# shield_Arduino.net
KiCad netlist of a schematic drawn in EAGLE
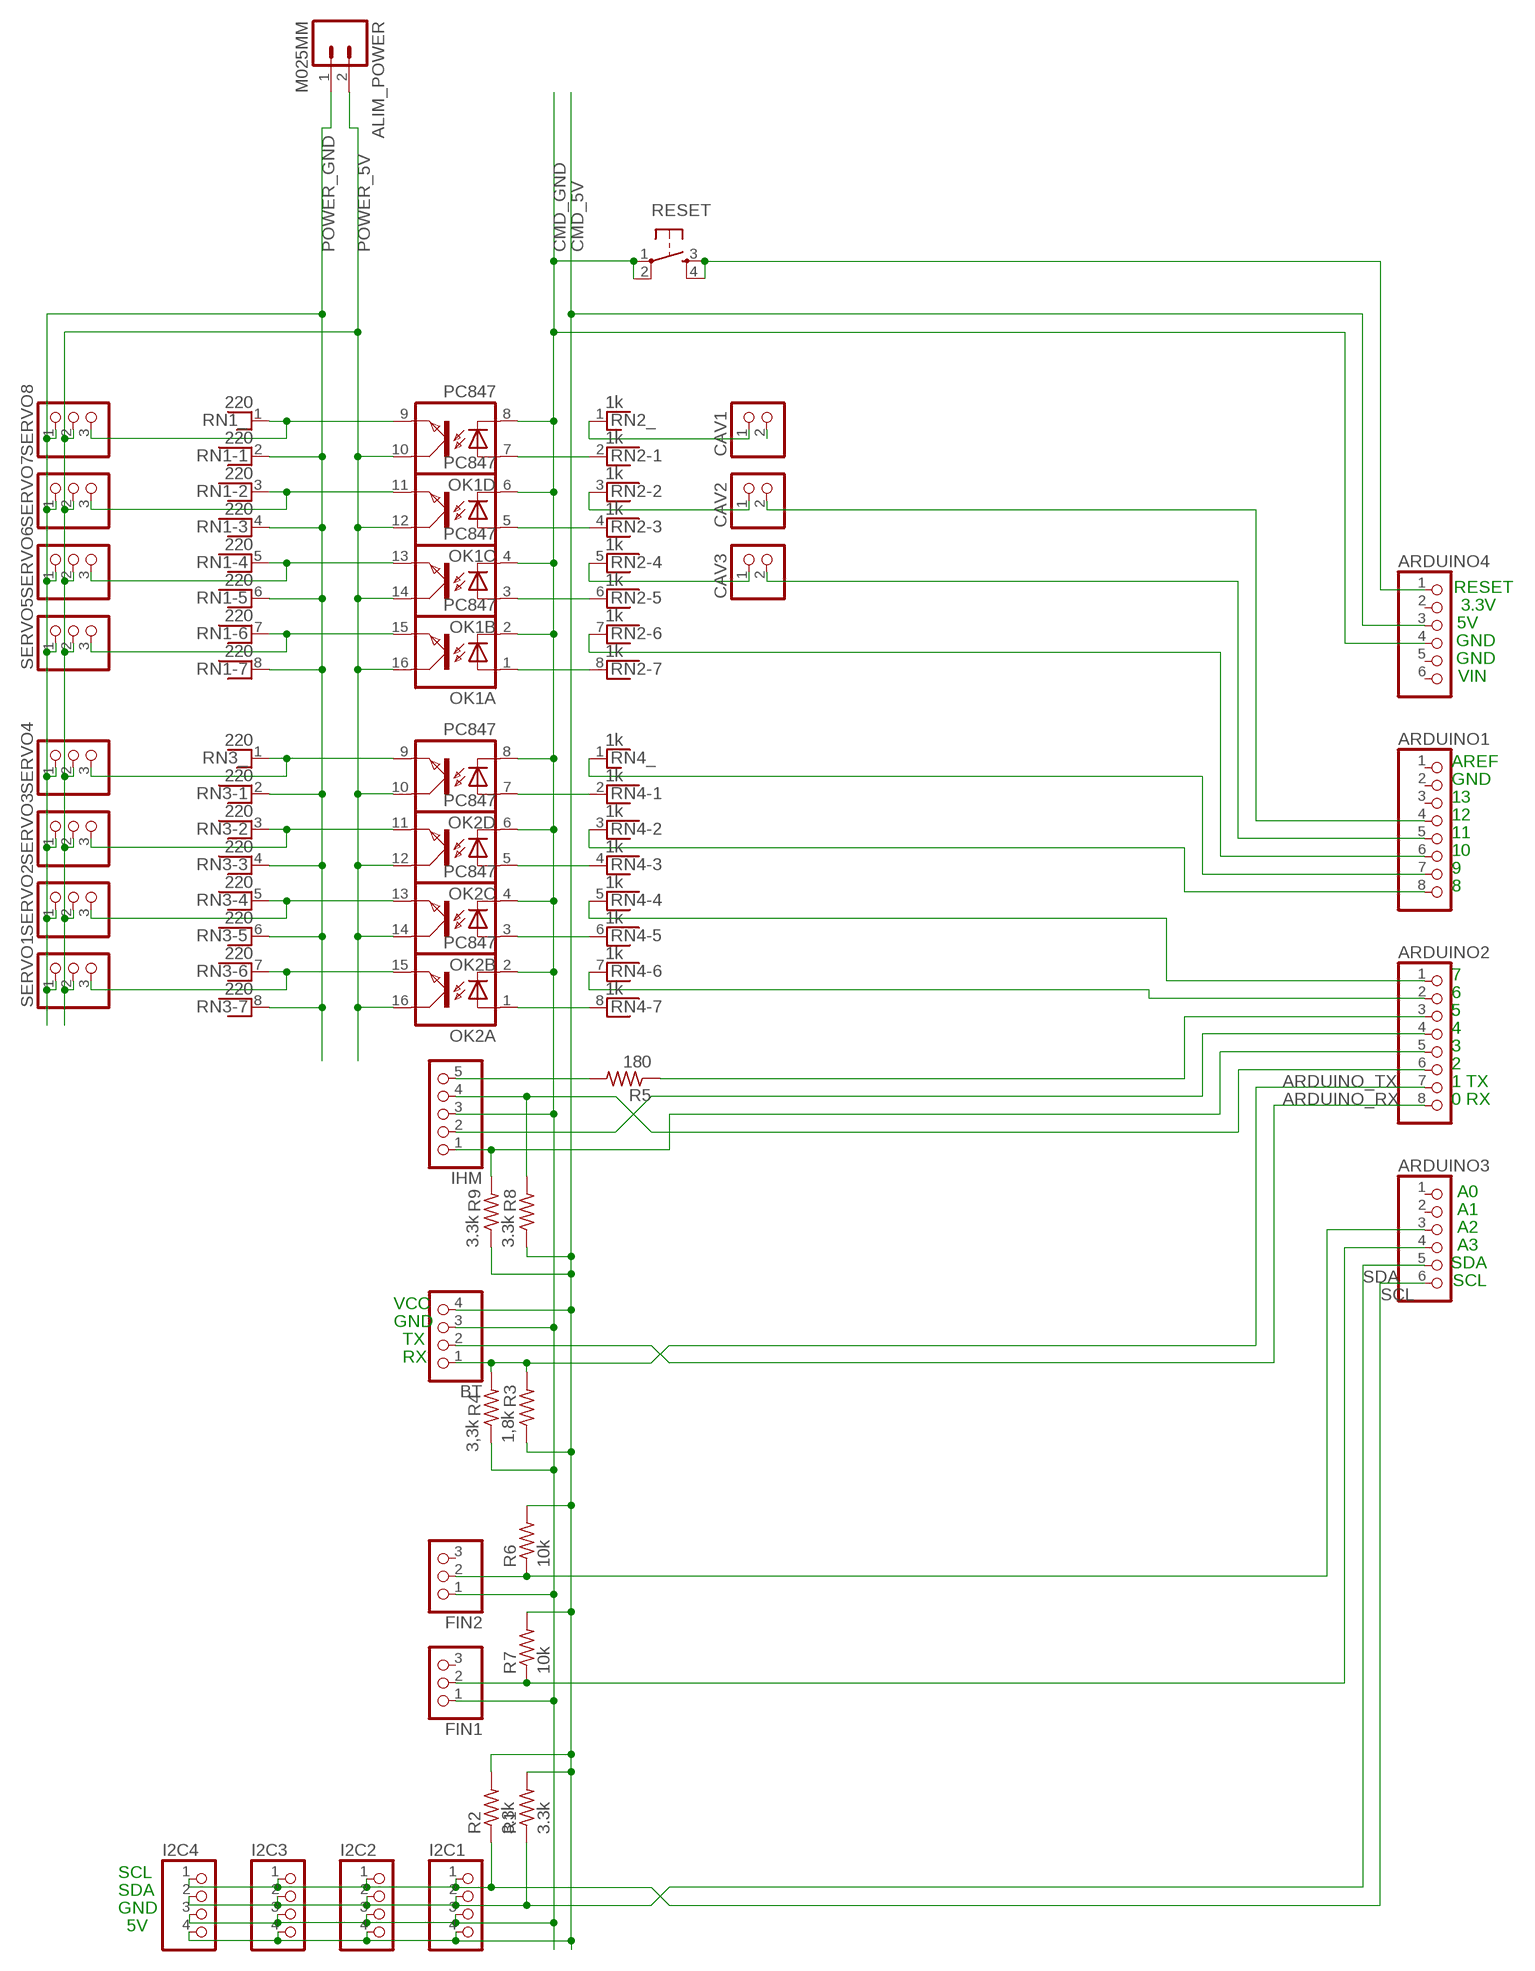
[diagram p0: schematic, sheet 1]

(export (version "E")
  (design (tool "Eeschema 10.0.6"))
  (components
    (comp (ref "ALIM_POWER")
      (value "M025MM")
      (footprint "eagle-import:SCREWTERMINAL-5MM-2")
      (libsource (lib "eagle-import") (part "M025MM"))
    )
    (comp (ref "ARDUINO1")
      (value "PINHD-1X8")
      (footprint "eagle-import:1X08")
      (libsource (lib "eagle-import") (part "PINHD-1X8"))
    )
    (comp (ref "ARDUINO2")
      (value "PINHD-1X8")
      (footprint "eagle-import:1X08")
      (libsource (lib "eagle-import") (part "PINHD-1X8"))
    )
    (comp (ref "ARDUINO3")
      (value "PINHD-1X6")
      (footprint "eagle-import:1X06")
      (libsource (lib "eagle-import") (part "PINHD-1X6"))
    )
    (comp (ref "ARDUINO4")
      (value "PINHD-1X6")
      (footprint "eagle-import:1X06")
      (libsource (lib "eagle-import") (part "PINHD-1X6"))
    )
    (comp (ref "BT")
      (value "PINHD-1X4")
      (footprint "eagle-import:1X04")
      (libsource (lib "eagle-import") (part "PINHD-1X4"))
    )
    (comp (ref "CAV1")
      (value "PINHD-1X2")
      (footprint "eagle-import:1X02")
      (libsource (lib "eagle-import") (part "PINHD-1X2"))
    )
    (comp (ref "CAV2")
      (value "PINHD-1X2")
      (footprint "eagle-import:1X02")
      (libsource (lib "eagle-import") (part "PINHD-1X2"))
    )
    (comp (ref "CAV3")
      (value "PINHD-1X2")
      (footprint "eagle-import:1X02")
      (libsource (lib "eagle-import") (part "PINHD-1X2"))
    )
    (comp (ref "FIN1")
      (value "PINHD-1X3")
      (footprint "eagle-import:1X03")
      (libsource (lib "eagle-import") (part "PINHD-1X3"))
    )
    (comp (ref "FIN2")
      (value "PINHD-1X3")
      (footprint "eagle-import:1X03")
      (libsource (lib "eagle-import") (part "PINHD-1X3"))
    )
    (comp (ref "I2C1")
      (value "PINHD-1X4")
      (footprint "eagle-import:1X04")
      (libsource (lib "eagle-import") (part "PINHD-1X4"))
    )
    (comp (ref "I2C2")
      (value "PINHD-1X4")
      (footprint "eagle-import:1X04")
      (libsource (lib "eagle-import") (part "PINHD-1X4"))
    )
    (comp (ref "I2C3")
      (value "PINHD-1X4")
      (footprint "eagle-import:1X04")
      (libsource (lib "eagle-import") (part "PINHD-1X4"))
    )
    (comp (ref "I2C4")
      (value "PINHD-1X4")
      (footprint "eagle-import:1X04")
      (libsource (lib "eagle-import") (part "PINHD-1X4"))
    )
    (comp (ref "IHM")
      (value "PINHD-1X5")
      (footprint "eagle-import:1X05")
      (libsource (lib "eagle-import") (part "PINHD-1X5"))
    )
    (comp (ref "OK1")
      (value "PC847")
      (footprint "eagle-import:DIL16")
      (libsource (lib "eagle-import") (part "PC847"))
    )
    (comp (ref "OK2")
      (value "PC847")
      (footprint "eagle-import:DIL16")
      (libsource (lib "eagle-import") (part "PC847"))
    )
    (comp (ref "R1")
      (value "3.3k")
      (footprint "eagle-import:0204_7")
      (libsource (lib "eagle-import") (part "R-US_0204/7"))
    )
    (comp (ref "R2")
      (value "3.3k")
      (footprint "eagle-import:0204_7")
      (libsource (lib "eagle-import") (part "R-US_0204/7"))
    )
    (comp (ref "R3")
      (value "1,8k")
      (footprint "eagle-import:0204_7")
      (libsource (lib "eagle-import") (part "R-US_0204/7"))
    )
    (comp (ref "R4")
      (value "3,3k")
      (footprint "eagle-import:0204_7")
      (libsource (lib "eagle-import") (part "R-US_0204/7"))
    )
    (comp (ref "R5")
      (value "180")
      (footprint "eagle-import:0204_7")
      (libsource (lib "eagle-import") (part "R-US_0204/7"))
    )
    (comp (ref "R6")
      (value "10k")
      (footprint "eagle-import:0204_7")
      (libsource (lib "eagle-import") (part "R-US_0204/7"))
    )
    (comp (ref "R7")
      (value "10k")
      (footprint "eagle-import:0204_7")
      (libsource (lib "eagle-import") (part "R-US_0204/7"))
    )
    (comp (ref "R8")
      (value "3.3k")
      (footprint "eagle-import:0204_7")
      (libsource (lib "eagle-import") (part "R-US_0204/7"))
    )
    (comp (ref "R9")
      (value "3.3k")
      (footprint "eagle-import:0204_7")
      (libsource (lib "eagle-import") (part "R-US_0204/7"))
    )
    (comp (ref "RESET")
      (value "TAC_SWITCHPTH")
      (footprint "eagle-import:TACTILE-PTH")
      (libsource (lib "eagle-import") (part "TAC_SWITCHPTH"))
    )
    (comp (ref "RN1")
      (value "220")
      (footprint "eagle-import:RN-8")
      (libsource (lib "eagle-import") (part "RNX7"))
    )
    (comp (ref "RN2")
      (value "1k")
      (footprint "eagle-import:RN-8")
      (libsource (lib "eagle-import") (part "RNX7"))
    )
    (comp (ref "RN3")
      (value "220")
      (footprint "eagle-import:RN-8")
      (libsource (lib "eagle-import") (part "RNX7"))
    )
    (comp (ref "RN4")
      (value "1k")
      (footprint "eagle-import:RN-8")
      (libsource (lib "eagle-import") (part "RNX7"))
    )
    (comp (ref "SERVO1")
      (value "PINHD-1X3")
      (footprint "eagle-import:1X03")
      (libsource (lib "eagle-import") (part "PINHD-1X3"))
    )
    (comp (ref "SERVO2")
      (value "PINHD-1X3")
      (footprint "eagle-import:1X03")
      (libsource (lib "eagle-import") (part "PINHD-1X3"))
    )
    (comp (ref "SERVO3")
      (value "PINHD-1X3")
      (footprint "eagle-import:1X03")
      (libsource (lib "eagle-import") (part "PINHD-1X3"))
    )
    (comp (ref "SERVO4")
      (value "PINHD-1X3")
      (footprint "eagle-import:1X03")
      (libsource (lib "eagle-import") (part "PINHD-1X3"))
    )
    (comp (ref "SERVO5")
      (value "PINHD-1X3")
      (footprint "eagle-import:1X03")
      (libsource (lib "eagle-import") (part "PINHD-1X3"))
    )
    (comp (ref "SERVO6")
      (value "PINHD-1X3")
      (footprint "eagle-import:1X03")
      (libsource (lib "eagle-import") (part "PINHD-1X3"))
    )
    (comp (ref "SERVO7")
      (value "PINHD-1X3")
      (footprint "eagle-import:1X03")
      (libsource (lib "eagle-import") (part "PINHD-1X3"))
    )
    (comp (ref "SERVO8")
      (value "PINHD-1X3")
      (footprint "eagle-import:1X03")
      (libsource (lib "eagle-import") (part "PINHD-1X3"))
    )
  )
  (nets
    (net (code "1") (name "/ARDUINO_RX") (class "Default")
      (node (ref "ARDUINO2") (pin "8") (pinfunction "8_8") (pintype "passive"))
      (node (ref "BT") (pin "2") (pinfunction "2_2") (pintype "passive"))
    )
    (net (code "2") (name "/ARDUINO_TX") (class "Default")
      (node (ref "ARDUINO2") (pin "7") (pinfunction "7_7") (pintype "passive"))
      (node (ref "BT") (pin "1") (pinfunction "1_1") (pintype "passive"))
      (node (ref "R3") (pin "2") (pinfunction "2_2") (pintype "passive"))
      (node (ref "R4") (pin "2") (pinfunction "2_2") (pintype "passive"))
    )
    (net (code "3") (name "/CMD_5V") (class "Default")
      (node (ref "ARDUINO4") (pin "3") (pinfunction "3_3") (pintype "passive"))
      (node (ref "BT") (pin "4") (pinfunction "4_4") (pintype "passive"))
      (node (ref "I2C1") (pin "4") (pinfunction "4_4") (pintype "passive"))
      (node (ref "I2C2") (pin "4") (pinfunction "4_4") (pintype "passive"))
      (node (ref "I2C3") (pin "4") (pinfunction "4_4") (pintype "passive"))
      (node (ref "I2C4") (pin "4") (pinfunction "4_4") (pintype "passive"))
      (node (ref "R1") (pin "2") (pinfunction "2_2") (pintype "passive"))
      (node (ref "R2") (pin "2") (pinfunction "2_2") (pintype "passive"))
      (node (ref "R3") (pin "1") (pinfunction "1_1") (pintype "passive"))
      (node (ref "R6") (pin "2") (pinfunction "2_2") (pintype "passive"))
      (node (ref "R7") (pin "2") (pinfunction "2_2") (pintype "passive"))
      (node (ref "R8") (pin "1") (pinfunction "1_1") (pintype "passive"))
      (node (ref "R9") (pin "1") (pinfunction "1_1") (pintype "passive"))
    )
    (net (code "4") (name "/CMD_GND") (class "Default")
      (node (ref "ARDUINO4") (pin "4") (pinfunction "4_4") (pintype "passive"))
      (node (ref "BT") (pin "3") (pinfunction "3_3") (pintype "passive"))
      (node (ref "FIN1") (pin "1") (pinfunction "1_1") (pintype "passive"))
      (node (ref "FIN2") (pin "1") (pinfunction "1_1") (pintype "passive"))
      (node (ref "I2C1") (pin "3") (pinfunction "3_3") (pintype "passive"))
      (node (ref "I2C2") (pin "3") (pinfunction "3_3") (pintype "passive"))
      (node (ref "I2C3") (pin "3") (pinfunction "3_3") (pintype "passive"))
      (node (ref "I2C4") (pin "3") (pinfunction "3_3") (pintype "passive"))
      (node (ref "IHM") (pin "3") (pinfunction "3_3") (pintype "passive"))
      (node (ref "OK1") (pin "2") (pinfunction "C_2") (pintype "passive"))
      (node (ref "OK1") (pin "4") (pinfunction "C_4") (pintype "passive"))
      (node (ref "OK1") (pin "6") (pinfunction "C_6") (pintype "passive"))
      (node (ref "OK1") (pin "8") (pinfunction "C_8") (pintype "passive"))
      (node (ref "OK2") (pin "2") (pinfunction "C_2") (pintype "passive"))
      (node (ref "OK2") (pin "4") (pinfunction "C_4") (pintype "passive"))
      (node (ref "OK2") (pin "6") (pinfunction "C_6") (pintype "passive"))
      (node (ref "OK2") (pin "8") (pinfunction "C_8") (pintype "passive"))
      (node (ref "R4") (pin "1") (pinfunction "1_1") (pintype "passive"))
      (node (ref "RESET") (pin "1") (pinfunction "1_1") (pintype "passive"))
      (node (ref "RESET") (pin "2") (pinfunction "2_2") (pintype "passive"))
    )
    (net (code "5") (name "/POWER_5V") (class "Default")
      (node (ref "ALIM_POWER") (pin "2") (pinfunction "2_2") (pintype "passive"))
      (node (ref "OK1") (pin "10") (pinfunction "COL_10") (pintype "passive"))
      (node (ref "OK1") (pin "12") (pinfunction "COL_12") (pintype "passive"))
      (node (ref "OK1") (pin "14") (pinfunction "COL_14") (pintype "passive"))
      (node (ref "OK1") (pin "16") (pinfunction "COL_16") (pintype "passive"))
      (node (ref "OK2") (pin "10") (pinfunction "COL_10") (pintype "passive"))
      (node (ref "OK2") (pin "12") (pinfunction "COL_12") (pintype "passive"))
      (node (ref "OK2") (pin "14") (pinfunction "COL_14") (pintype "passive"))
      (node (ref "OK2") (pin "16") (pinfunction "COL_16") (pintype "passive"))
      (node (ref "SERVO1") (pin "2") (pinfunction "2_2") (pintype "passive"))
      (node (ref "SERVO2") (pin "2") (pinfunction "2_2") (pintype "passive"))
      (node (ref "SERVO3") (pin "2") (pinfunction "2_2") (pintype "passive"))
      (node (ref "SERVO4") (pin "2") (pinfunction "2_2") (pintype "passive"))
      (node (ref "SERVO5") (pin "2") (pinfunction "2_2") (pintype "passive"))
      (node (ref "SERVO6") (pin "2") (pinfunction "2_2") (pintype "passive"))
      (node (ref "SERVO7") (pin "2") (pinfunction "2_2") (pintype "passive"))
      (node (ref "SERVO8") (pin "2") (pinfunction "2_2") (pintype "passive"))
    )
    (net (code "6") (name "/POWER_GND") (class "Default")
      (node (ref "ALIM_POWER") (pin "1") (pinfunction "1_1") (pintype "passive"))
      (node (ref "RN1") (pin "2") (pinfunction "1_2") (pintype "passive"))
      (node (ref "RN1") (pin "4") (pinfunction "1_4") (pintype "passive"))
      (node (ref "RN1") (pin "6") (pinfunction "1_6") (pintype "passive"))
      (node (ref "RN1") (pin "8") (pinfunction "1_8") (pintype "passive"))
      (node (ref "RN3") (pin "2") (pinfunction "1_2") (pintype "passive"))
      (node (ref "RN3") (pin "4") (pinfunction "1_4") (pintype "passive"))
      (node (ref "RN3") (pin "6") (pinfunction "1_6") (pintype "passive"))
      (node (ref "RN3") (pin "8") (pinfunction "1_8") (pintype "passive"))
      (node (ref "SERVO1") (pin "1") (pinfunction "1_1") (pintype "passive"))
      (node (ref "SERVO2") (pin "1") (pinfunction "1_1") (pintype "passive"))
      (node (ref "SERVO3") (pin "1") (pinfunction "1_1") (pintype "passive"))
      (node (ref "SERVO4") (pin "1") (pinfunction "1_1") (pintype "passive"))
      (node (ref "SERVO5") (pin "1") (pinfunction "1_1") (pintype "passive"))
      (node (ref "SERVO6") (pin "1") (pinfunction "1_1") (pintype "passive"))
      (node (ref "SERVO7") (pin "1") (pinfunction "1_1") (pintype "passive"))
      (node (ref "SERVO8") (pin "1") (pinfunction "1_1") (pintype "passive"))
    )
    (net (code "7") (name "/SCL") (class "Default")
      (node (ref "ARDUINO3") (pin "6") (pinfunction "6_6") (pintype "passive"))
      (node (ref "I2C1") (pin "1") (pinfunction "1_1") (pintype "passive"))
      (node (ref "I2C2") (pin "1") (pinfunction "1_1") (pintype "passive"))
      (node (ref "I2C3") (pin "1") (pinfunction "1_1") (pintype "passive"))
      (node (ref "I2C4") (pin "1") (pinfunction "1_1") (pintype "passive"))
      (node (ref "R2") (pin "1") (pinfunction "1_1") (pintype "passive"))
    )
    (net (code "8") (name "/SDA") (class "Default")
      (node (ref "ARDUINO3") (pin "5") (pinfunction "5_5") (pintype "passive"))
      (node (ref "I2C1") (pin "2") (pinfunction "2_2") (pintype "passive"))
      (node (ref "I2C2") (pin "2") (pinfunction "2_2") (pintype "passive"))
      (node (ref "I2C3") (pin "2") (pinfunction "2_2") (pintype "passive"))
      (node (ref "I2C4") (pin "2") (pinfunction "2_2") (pintype "passive"))
      (node (ref "R1") (pin "1") (pinfunction "1_1") (pintype "passive"))
    )
    (net (code "9") (name "Net-(ARDUINO1-Pad4)") (class "Default")
      (node (ref "ARDUINO1") (pin "4") (pinfunction "4_4") (pintype "passive"))
      (node (ref "CAV2") (pin "2") (pinfunction "2_2") (pintype "passive"))
    )
    (net (code "10") (name "Net-(ARDUINO1-Pad5)") (class "Default")
      (node (ref "ARDUINO1") (pin "5") (pinfunction "5_5") (pintype "passive"))
      (node (ref "CAV3") (pin "2") (pinfunction "2_2") (pintype "passive"))
    )
    (net (code "11") (name "Net-(ARDUINO1-Pad7)") (class "Default")
      (node (ref "ARDUINO1") (pin "7") (pinfunction "7_7") (pintype "passive"))
      (node (ref "RN4") (pin "1") (pinfunction "1_1") (pintype "passive"))
    )
    (net (code "12") (name "Net-(ARDUINO2-Pad3)") (class "Default")
      (node (ref "ARDUINO2") (pin "3") (pinfunction "3_3") (pintype "passive"))
      (node (ref "R5") (pin "1") (pinfunction "1_1") (pintype "passive"))
    )
    (net (code "13") (name "Net-(ARDUINO2-Pad4)") (class "Default")
      (node (ref "ARDUINO2") (pin "4") (pinfunction "4_4") (pintype "passive"))
      (node (ref "IHM") (pin "2") (pinfunction "2_2") (pintype "passive"))
    )
    (net (code "14") (name "Net-(ARDUINO2-Pad5)") (class "Default")
      (node (ref "ARDUINO2") (pin "5") (pinfunction "5_5") (pintype "passive"))
      (node (ref "IHM") (pin "1") (pinfunction "1_1") (pintype "passive"))
      (node (ref "R9") (pin "2") (pinfunction "2_2") (pintype "passive"))
    )
    (net (code "15") (name "Net-(ARDUINO2-Pad6)") (class "Default")
      (node (ref "ARDUINO2") (pin "6") (pinfunction "6_6") (pintype "passive"))
      (node (ref "IHM") (pin "4") (pinfunction "4_4") (pintype "passive"))
      (node (ref "R8") (pin "2") (pinfunction "2_2") (pintype "passive"))
    )
    (net (code "16") (name "Net-(ARDUINO3-Pad3)") (class "Default")
      (node (ref "ARDUINO3") (pin "3") (pinfunction "3_3") (pintype "passive"))
      (node (ref "FIN2") (pin "2") (pinfunction "2_2") (pintype "passive"))
      (node (ref "R6") (pin "1") (pinfunction "1_1") (pintype "passive"))
    )
    (net (code "17") (name "Net-(ARDUINO3-Pad4)") (class "Default")
      (node (ref "ARDUINO3") (pin "4") (pinfunction "4_4") (pintype "passive"))
      (node (ref "FIN1") (pin "2") (pinfunction "2_2") (pintype "passive"))
      (node (ref "R7") (pin "1") (pinfunction "1_1") (pintype "passive"))
    )
    (net (code "18") (name "Net-(ARDUINO4-Pad1)") (class "Default")
      (node (ref "ARDUINO4") (pin "1") (pinfunction "1_1") (pintype "passive"))
      (node (ref "RESET") (pin "3") (pinfunction "3_3") (pintype "passive"))
      (node (ref "RESET") (pin "4") (pinfunction "4_4") (pintype "passive"))
    )
    (net (code "19") (name "Net-(CAV1-Pad1)") (class "Default")
      (node (ref "CAV1") (pin "1") (pinfunction "1_1") (pintype "passive"))
      (node (ref "RN2") (pin "1") (pinfunction "1_1") (pintype "passive"))
    )
    (net (code "20") (name "Net-(IHM-Pad5)") (class "Default")
      (node (ref "IHM") (pin "5") (pinfunction "5_5") (pintype "passive"))
      (node (ref "R5") (pin "2") (pinfunction "2_2") (pintype "passive"))
    )
    (net (code "21") (name "Net-(OK1A-A)") (class "Default")
      (node (ref "OK1") (pin "1") (pinfunction "A_1") (pintype "passive"))
      (node (ref "RN2") (pin "8") (pinfunction "1_8") (pintype "passive"))
    )
    (net (code "22") (name "Net-(OK1A-EMIT)") (class "Default")
      (node (ref "OK1") (pin "15") (pinfunction "EMIT_15") (pintype "passive"))
      (node (ref "RN1") (pin "7") (pinfunction "1_7") (pintype "passive"))
      (node (ref "SERVO5") (pin "3") (pinfunction "3_3") (pintype "passive"))
    )
    (net (code "23") (name "Net-(OK1B-A)") (class "Default")
      (node (ref "OK1") (pin "3") (pinfunction "A_3") (pintype "passive"))
      (node (ref "RN2") (pin "6") (pinfunction "1_6") (pintype "passive"))
    )
    (net (code "24") (name "Net-(OK1B-EMIT)") (class "Default")
      (node (ref "OK1") (pin "13") (pinfunction "EMIT_13") (pintype "passive"))
      (node (ref "RN1") (pin "5") (pinfunction "1_5") (pintype "passive"))
      (node (ref "SERVO6") (pin "3") (pinfunction "3_3") (pintype "passive"))
    )
    (net (code "25") (name "Net-(OK1C-A)") (class "Default")
      (node (ref "OK1") (pin "5") (pinfunction "A_5") (pintype "passive"))
      (node (ref "RN2") (pin "4") (pinfunction "1_4") (pintype "passive"))
    )
    (net (code "26") (name "Net-(OK1C-EMIT)") (class "Default")
      (node (ref "OK1") (pin "11") (pinfunction "EMIT_11") (pintype "passive"))
      (node (ref "RN1") (pin "3") (pinfunction "1_3") (pintype "passive"))
      (node (ref "SERVO7") (pin "3") (pinfunction "3_3") (pintype "passive"))
    )
    (net (code "27") (name "Net-(OK1D-A)") (class "Default")
      (node (ref "OK1") (pin "7") (pinfunction "A_7") (pintype "passive"))
      (node (ref "RN2") (pin "2") (pinfunction "1_2") (pintype "passive"))
    )
    (net (code "28") (name "Net-(OK1D-EMIT)") (class "Default")
      (node (ref "OK1") (pin "9") (pinfunction "EMIT_9") (pintype "passive"))
      (node (ref "RN1") (pin "1") (pinfunction "1_1") (pintype "passive"))
      (node (ref "SERVO8") (pin "3") (pinfunction "3_3") (pintype "passive"))
    )
    (net (code "29") (name "Net-(OK2A-A)") (class "Default")
      (node (ref "OK2") (pin "1") (pinfunction "A_1") (pintype "passive"))
      (node (ref "RN4") (pin "8") (pinfunction "1_8") (pintype "passive"))
    )
    (net (code "30") (name "Net-(OK2A-EMIT)") (class "Default")
      (node (ref "OK2") (pin "15") (pinfunction "EMIT_15") (pintype "passive"))
      (node (ref "RN3") (pin "7") (pinfunction "1_7") (pintype "passive"))
      (node (ref "SERVO1") (pin "3") (pinfunction "3_3") (pintype "passive"))
    )
    (net (code "31") (name "Net-(OK2B-A)") (class "Default")
      (node (ref "OK2") (pin "3") (pinfunction "A_3") (pintype "passive"))
      (node (ref "RN4") (pin "6") (pinfunction "1_6") (pintype "passive"))
    )
    (net (code "32") (name "Net-(OK2B-EMIT)") (class "Default")
      (node (ref "OK2") (pin "13") (pinfunction "EMIT_13") (pintype "passive"))
      (node (ref "RN3") (pin "5") (pinfunction "1_5") (pintype "passive"))
      (node (ref "SERVO2") (pin "3") (pinfunction "3_3") (pintype "passive"))
    )
    (net (code "33") (name "Net-(OK2C-A)") (class "Default")
      (node (ref "OK2") (pin "5") (pinfunction "A_5") (pintype "passive"))
      (node (ref "RN4") (pin "4") (pinfunction "1_4") (pintype "passive"))
    )
    (net (code "34") (name "Net-(OK2C-EMIT)") (class "Default")
      (node (ref "OK2") (pin "11") (pinfunction "EMIT_11") (pintype "passive"))
      (node (ref "RN3") (pin "3") (pinfunction "1_3") (pintype "passive"))
      (node (ref "SERVO3") (pin "3") (pinfunction "3_3") (pintype "passive"))
    )
    (net (code "35") (name "Net-(OK2D-A)") (class "Default")
      (node (ref "OK2") (pin "7") (pinfunction "A_7") (pintype "passive"))
      (node (ref "RN4") (pin "2") (pinfunction "1_2") (pintype "passive"))
    )
    (net (code "36") (name "Net-(OK2D-EMIT)") (class "Default")
      (node (ref "OK2") (pin "9") (pinfunction "EMIT_9") (pintype "passive"))
      (node (ref "RN3") (pin "1") (pinfunction "1_1") (pintype "passive"))
      (node (ref "SERVO4") (pin "3") (pinfunction "3_3") (pintype "passive"))
    )
    (net (code "37") (name "Net-(RN2B-1)") (class "Default")
      (node (ref "CAV2") (pin "1") (pinfunction "1_1") (pintype "passive"))
      (node (ref "RN2") (pin "3") (pinfunction "1_3") (pintype "passive"))
    )
    (net (code "38") (name "Net-(RN2D-1)") (class "Default")
      (node (ref "CAV3") (pin "1") (pinfunction "1_1") (pintype "passive"))
      (node (ref "RN2") (pin "5") (pinfunction "1_5") (pintype "passive"))
    )
    (net (code "39") (name "Net-(RN2F-1)") (class "Default")
      (node (ref "ARDUINO1") (pin "6") (pinfunction "6_6") (pintype "passive"))
      (node (ref "RN2") (pin "7") (pinfunction "1_7") (pintype "passive"))
    )
    (net (code "40") (name "Net-(RN4B-1)") (class "Default")
      (node (ref "ARDUINO1") (pin "8") (pinfunction "8_8") (pintype "passive"))
      (node (ref "RN4") (pin "3") (pinfunction "1_3") (pintype "passive"))
    )
    (net (code "41") (name "Net-(RN4D-1)") (class "Default")
      (node (ref "ARDUINO2") (pin "1") (pinfunction "1_1") (pintype "passive"))
      (node (ref "RN4") (pin "5") (pinfunction "1_5") (pintype "passive"))
    )
    (net (code "42") (name "Net-(RN4F-1)") (class "Default")
      (node (ref "ARDUINO2") (pin "2") (pinfunction "2_2") (pintype "passive"))
      (node (ref "RN4") (pin "7") (pinfunction "1_7") (pintype "passive"))
    )
    (net (code "43") (name "unconnected-(ARDUINO1-Pad1)") (class "Default")
      (node (ref "ARDUINO1") (pin "1") (pinfunction "1_1") (pintype "passive"))
    )
    (net (code "44") (name "unconnected-(ARDUINO1-Pad2)") (class "Default")
      (node (ref "ARDUINO1") (pin "2") (pinfunction "2_2") (pintype "passive"))
    )
    (net (code "45") (name "unconnected-(ARDUINO1-Pad3)") (class "Default")
      (node (ref "ARDUINO1") (pin "3") (pinfunction "3_3") (pintype "passive"))
    )
    (net (code "46") (name "unconnected-(ARDUINO3-Pad1)") (class "Default")
      (node (ref "ARDUINO3") (pin "1") (pinfunction "1_1") (pintype "passive"))
    )
    (net (code "47") (name "unconnected-(ARDUINO3-Pad2)") (class "Default")
      (node (ref "ARDUINO3") (pin "2") (pinfunction "2_2") (pintype "passive"))
    )
    (net (code "48") (name "unconnected-(ARDUINO4-Pad2)") (class "Default")
      (node (ref "ARDUINO4") (pin "2") (pinfunction "2_2") (pintype "passive"))
    )
    (net (code "49") (name "unconnected-(ARDUINO4-Pad5)") (class "Default")
      (node (ref "ARDUINO4") (pin "5") (pinfunction "5_5") (pintype "passive"))
    )
    (net (code "50") (name "unconnected-(ARDUINO4-Pad6)") (class "Default")
      (node (ref "ARDUINO4") (pin "6") (pinfunction "6_6") (pintype "passive"))
    )
    (net (code "51") (name "unconnected-(CAV1-Pad2)") (class "Default")
      (node (ref "CAV1") (pin "2") (pinfunction "2_2") (pintype "passive"))
    )
    (net (code "52") (name "unconnected-(FIN1-Pad3)") (class "Default")
      (node (ref "FIN1") (pin "3") (pinfunction "3_3") (pintype "passive"))
    )
    (net (code "53") (name "unconnected-(FIN2-Pad3)") (class "Default")
      (node (ref "FIN2") (pin "3") (pinfunction "3_3") (pintype "passive"))
    )
  )
)
